# relais_schaltung.net
KiCad netlist of a schematic drawn in Altium Designer
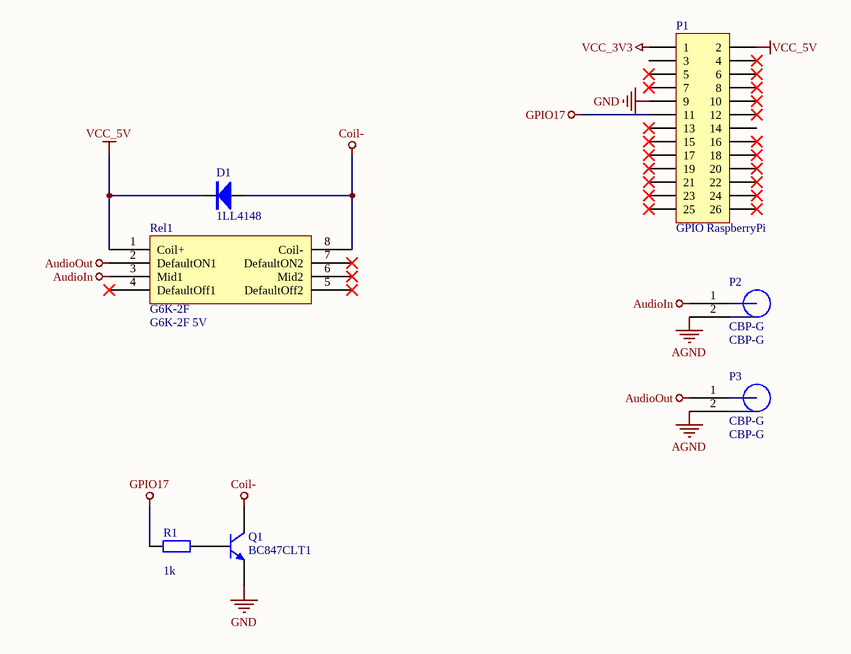
[diagram p0: relais_schaltung.SchDoc]

(export (version "E")
  (design (tool "Eeschema 10.0.6"))
  (components
    (comp (ref "D1")
      (value "1LL4148")
      (footprint "1206")
      (description "Diode")
      (libsource (lib "FKA_DXP_Source") (part "1LL4148"))
    )
    (comp (ref "P1")
      (value "GPIO RaspberryPi")
      (footprint "HDR2X13")
      (description "Header, 13-Pin, Dual row")
      (fields (field (name "PUBLISHER") "Altium Limited"))
      (libsource (lib "Miscellaneous Connectors") (part "Header 13X2"))
    )
    (comp (ref "P2")
      (value "CBP-G")
      (footprint "Cinch")
      (fields (field (name "REICHELT") "CBP-G"))
      (libsource (lib "relais_schaltung") (part "Cinch Print"))
    )
    (comp (ref "P3")
      (value "CBP-G")
      (footprint "Cinch")
      (fields (field (name "REICHELT") "CBP-G"))
      (libsource (lib "relais_schaltung") (part "Cinch Print"))
    )
    (comp (ref "Q1")
      (value "BC847CLT1")
      (footprint "SOT-23")
      (description "General Purpose Transistor NPN Silicon")
      (fields (field (name "PUBLISHER") "Altium Limited"))
      (libsource (lib "Motorola Discrete BJT") (part "BC847CLT1"))
    )
    (comp (ref "R1")
      (value "1k")
      (footprint "0805")
      (description "Resistor")
      (fields (field (name "PUBLISHER") "Altium Limited"))
      (libsource (lib "Miscellaneous Devices") (part "Res2"))
    )
    (comp (ref "Rel1")
      (value "G6K-2F")
      (footprint "G6K-2F")
      (fields (field (name "REICHELT") "G6K-2F 5V"))
      (libsource (lib "relais_schaltung") (part "G6K-2F"))
    )
  )
  (nets
    (net (code "1") (name "AGND") (class "Default")
      (node (ref "P2") (pin "2") (pinfunction "GND_2") (pintype "passive"))
      (node (ref "P3") (pin "2") (pinfunction "GND_2") (pintype "passive"))
    )
    (net (code "2") (name "AudioIn") (class "Default")
      (node (ref "P2") (pin "1") (pinfunction "Sig_1") (pintype "passive"))
      (node (ref "Rel1") (pin "3") (pinfunction "Mid1_3") (pintype "passive"))
    )
    (net (code "3") (name "AudioOut") (class "Default")
      (node (ref "P3") (pin "1") (pinfunction "Sig_1") (pintype "passive"))
      (node (ref "Rel1") (pin "2") (pinfunction "DefaultON1_2") (pintype "passive"))
    )
    (net (code "4") (name "Coil-") (class "Default")
      (node (ref "D1") (pin "1") (pinfunction "A_1") (pintype "passive"))
      (node (ref "Q1") (pin "3") (pinfunction "C_3") (pintype "passive"))
      (node (ref "Rel1") (pin "8") (pinfunction "Coil-_8") (pintype "passive"))
    )
    (net (code "5") (name "GND") (class "Default")
      (node (ref "P1") (pin "9") (pinfunction "9_9") (pintype "passive"))
      (node (ref "Q1") (pin "2") (pinfunction "E_2") (pintype "passive"))
    )
    (net (code "6") (name "GPIO17") (class "Default")
      (node (ref "P1") (pin "11") (pinfunction "11_11") (pintype "passive"))
      (node (ref "R1") (pin "1") (pinfunction "1_1") (pintype "passive"))
    )
    (net (code "7") (name "Net-(Q1-B)") (class "Default")
      (node (ref "Q1") (pin "1") (pinfunction "B_1") (pintype "passive"))
      (node (ref "R1") (pin "2") (pinfunction "2_2") (pintype "passive"))
    )
    (net (code "8") (name "VCC_3V3") (class "Default")
      (node (ref "P1") (pin "1") (pinfunction "1_1") (pintype "passive"))
    )
    (net (code "9") (name "VCC_5V") (class "Default")
      (node (ref "D1") (pin "2") (pinfunction "K_2") (pintype "passive"))
      (node (ref "P1") (pin "2") (pinfunction "2_2") (pintype "passive"))
      (node (ref "Rel1") (pin "1") (pinfunction "Coil+_1") (pintype "passive"))
    )
    (net (code "10") (name "unconnected-(P1-Pad3)") (class "Default")
      (node (ref "P1") (pin "3") (pinfunction "3_3") (pintype "passive"))
    )
    (net (code "11") (name "unconnected-(P1-Pad4)") (class "Default")
      (node (ref "P1") (pin "4") (pinfunction "4_4") (pintype "passive+no_connect"))
    )
    (net (code "12") (name "unconnected-(P1-Pad5)") (class "Default")
      (node (ref "P1") (pin "5") (pinfunction "5_5") (pintype "passive+no_connect"))
    )
    (net (code "13") (name "unconnected-(P1-Pad6)") (class "Default")
      (node (ref "P1") (pin "6") (pinfunction "6_6") (pintype "passive+no_connect"))
    )
    (net (code "14") (name "unconnected-(P1-Pad7)") (class "Default")
      (node (ref "P1") (pin "7") (pinfunction "7_7") (pintype "passive+no_connect"))
    )
    (net (code "15") (name "unconnected-(P1-Pad8)") (class "Default")
      (node (ref "P1") (pin "8") (pinfunction "8_8") (pintype "passive+no_connect"))
    )
    (net (code "16") (name "unconnected-(P1-Pad10)") (class "Default")
      (node (ref "P1") (pin "10") (pinfunction "10_10") (pintype "passive+no_connect"))
    )
    (net (code "17") (name "unconnected-(P1-Pad12)") (class "Default")
      (node (ref "P1") (pin "12") (pinfunction "12_12") (pintype "passive+no_connect"))
    )
    (net (code "18") (name "unconnected-(P1-Pad13)") (class "Default")
      (node (ref "P1") (pin "13") (pinfunction "13_13") (pintype "passive+no_connect"))
    )
    (net (code "19") (name "unconnected-(P1-Pad14)") (class "Default")
      (node (ref "P1") (pin "14") (pinfunction "14_14") (pintype "passive"))
    )
    (net (code "20") (name "unconnected-(P1-Pad15)") (class "Default")
      (node (ref "P1") (pin "15") (pinfunction "15_15") (pintype "passive+no_connect"))
    )
    (net (code "21") (name "unconnected-(P1-Pad16)") (class "Default")
      (node (ref "P1") (pin "16") (pinfunction "16_16") (pintype "passive+no_connect"))
    )
    (net (code "22") (name "unconnected-(P1-Pad17)") (class "Default")
      (node (ref "P1") (pin "17") (pinfunction "17_17") (pintype "passive+no_connect"))
    )
    (net (code "23") (name "unconnected-(P1-Pad18)") (class "Default")
      (node (ref "P1") (pin "18") (pinfunction "18_18") (pintype "passive+no_connect"))
    )
    (net (code "24") (name "unconnected-(P1-Pad19)") (class "Default")
      (node (ref "P1") (pin "19") (pinfunction "19_19") (pintype "passive+no_connect"))
    )
    (net (code "25") (name "unconnected-(P1-Pad20)") (class "Default")
      (node (ref "P1") (pin "20") (pinfunction "20_20") (pintype "passive+no_connect"))
    )
    (net (code "26") (name "unconnected-(P1-Pad21)") (class "Default")
      (node (ref "P1") (pin "21") (pinfunction "21_21") (pintype "passive+no_connect"))
    )
    (net (code "27") (name "unconnected-(P1-Pad22)") (class "Default")
      (node (ref "P1") (pin "22") (pinfunction "22_22") (pintype "passive+no_connect"))
    )
    (net (code "28") (name "unconnected-(P1-Pad23)") (class "Default")
      (node (ref "P1") (pin "23") (pinfunction "23_23") (pintype "passive+no_connect"))
    )
    (net (code "29") (name "unconnected-(P1-Pad24)") (class "Default")
      (node (ref "P1") (pin "24") (pinfunction "24_24") (pintype "passive+no_connect"))
    )
    (net (code "30") (name "unconnected-(P1-Pad25)") (class "Default")
      (node (ref "P1") (pin "25") (pinfunction "25_25") (pintype "passive+no_connect"))
    )
    (net (code "31") (name "unconnected-(P1-Pad26)") (class "Default")
      (node (ref "P1") (pin "26") (pinfunction "26_26") (pintype "passive+no_connect"))
    )
    (net (code "32") (name "unconnected-(Rel1-DefaultON2-Pad7)") (class "Default")
      (node (ref "Rel1") (pin "7") (pinfunction "DefaultON2_7") (pintype "passive+no_connect"))
    )
    (net (code "33") (name "unconnected-(Rel1-DefaultOff1-Pad4)") (class "Default")
      (node (ref "Rel1") (pin "4") (pinfunction "DefaultOff1_4") (pintype "passive+no_connect"))
    )
    (net (code "34") (name "unconnected-(Rel1-DefaultOff2-Pad5)") (class "Default")
      (node (ref "Rel1") (pin "5") (pinfunction "DefaultOff2_5") (pintype "passive+no_connect"))
    )
    (net (code "35") (name "unconnected-(Rel1-Mid2-Pad6)") (class "Default")
      (node (ref "Rel1") (pin "6") (pinfunction "Mid2_6") (pintype "passive+no_connect"))
    )
  )
)
